# gateway.net
KiCad netlist of a schematic drawn in Altium Designer
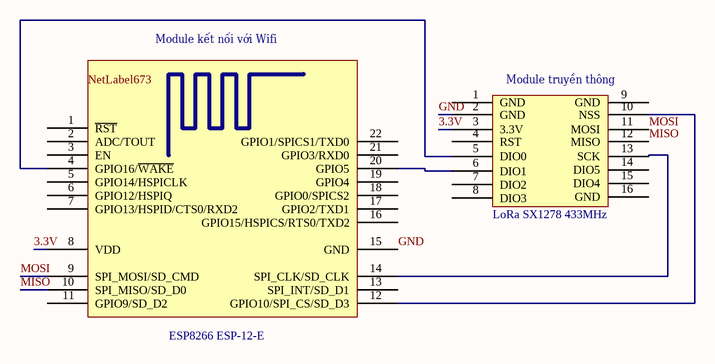
[diagram p0: gateway.SchDoc]

(export (version "E")
  (design (tool "Eeschema 10.0.6"))
  (components
    (comp (ref "Module kết nối với Wifi")
      (value "ESP8266 ESP-12-E")
      (footprint "ESP8266:ESP8266 ESP-12-E")
      (libsource (lib "ESP8266") (part "ESP8266 ESP-12-E"))
    )
    (comp (ref "Module truyền thông")
      (value "LoRa SX1278 433MHz")
      (footprint "PCBLoRa")
      (libsource (lib "LoRa") (part "Component_1"))
    )
  )
  (nets
    (net (code "1") (name "/3.3V") (class "Default")
      (node (ref "Module kết nối với Wifi") (pin "8") (pinfunction "VDD_8") (pintype "passive"))
      (node (ref "Module truyền thông") (pin "3") (pinfunction "3.3V_3") (pintype "passive"))
    )
    (net (code "2") (name "/GND") (class "Default")
      (node (ref "Module kết nối với Wifi") (pin "15") (pinfunction "GND_15") (pintype "passive"))
      (node (ref "Module truyền thông") (pin "2") (pinfunction "GND_2") (pintype "passive"))
    )
    (net (code "3") (name "/MISO") (class "Default")
      (node (ref "Module kết nối với Wifi") (pin "10") (pinfunction "SPI_MISO/SD_D0_10") (pintype "passive"))
      (node (ref "Module truyền thông") (pin "12") (pinfunction "MISO_12") (pintype "passive"))
    )
    (net (code "4") (name "/MOSI") (class "Default")
      (node (ref "Module kết nối với Wifi") (pin "9") (pinfunction "SPI_MOSI/SD_CMD_9") (pintype "passive"))
      (node (ref "Module truyền thông") (pin "11") (pinfunction "MOSI_11") (pintype "passive"))
    )
    (net (code "6") (name "Net-(Module kết nối với Wifi-GPIO5)") (class "Default")
      (node (ref "Module kết nối với Wifi") (pin "20") (pinfunction "GPIO5_20") (pintype "passive"))
      (node (ref "Module truyền thông") (pin "6") (pinfunction "DIO1_6") (pintype "passive"))
    )
    (net (code "7") (name "Net-(Module kết nối với Wifi-GPIO10{slash}SPI_CS{slash}SD_D3)") (class "Default")
      (node (ref "Module kết nối với Wifi") (pin "12") (pinfunction "GPIO10/SPI_CS/SD_D3_12") (pintype "passive"))
      (node (ref "Module truyền thông") (pin "10") (pinfunction "NSS_10") (pintype "passive"))
    )
    (net (code "8") (name "Net-(Module kết nối với Wifi-GPIO16{slash}~{WAKE})") (class "Default")
      (node (ref "Module kết nối với Wifi") (pin "4") (pinfunction "GPIO16/~{WAKE}_4") (pintype "passive"))
      (node (ref "Module truyền thông") (pin "5") (pinfunction "DIO0_5") (pintype "passive"))
    )
    (net (code "9") (name "Net-(Module kết nối với Wifi-SPI_CLK{slash}SD_CLK)") (class "Default")
      (node (ref "Module kết nối với Wifi") (pin "14") (pinfunction "SPI_CLK/SD_CLK_14") (pintype "passive"))
      (node (ref "Module truyền thông") (pin "13") (pinfunction "SCK_13") (pintype "passive"))
    )
    (net (code "10") (name "unconnected-(Module kết nối với Wifi-ADC{slash}TOUT-Pad2)") (class "Default")
      (node (ref "Module kết nối với Wifi") (pin "2") (pinfunction "ADC/TOUT_2") (pintype "passive"))
    )
    (net (code "11") (name "unconnected-(Module kết nối với Wifi-EN-Pad3)") (class "Default")
      (node (ref "Module kết nối với Wifi") (pin "3") (pinfunction "EN_3") (pintype "passive"))
    )
    (net (code "12") (name "unconnected-(Module kết nối với Wifi-GPIO0{slash}SPICS2-Pad18)") (class "Default")
      (node (ref "Module kết nối với Wifi") (pin "18") (pinfunction "GPIO0/SPICS2_18") (pintype "passive"))
    )
    (net (code "13") (name "unconnected-(Module kết nối với Wifi-GPIO1{slash}SPICS1{slash}TXD0-Pad22)") (class "Default")
      (node (ref "Module kết nối với Wifi") (pin "22") (pinfunction "GPIO1/SPICS1/TXD0_22") (pintype "passive"))
    )
    (net (code "14") (name "unconnected-(Module kết nối với Wifi-GPIO2{slash}TXD1-Pad17)") (class "Default")
      (node (ref "Module kết nối với Wifi") (pin "17") (pinfunction "GPIO2/TXD1_17") (pintype "passive"))
    )
    (net (code "15") (name "unconnected-(Module kết nối với Wifi-GPIO3{slash}RXD0-Pad21)") (class "Default")
      (node (ref "Module kết nối với Wifi") (pin "21") (pinfunction "GPIO3/RXD0_21") (pintype "passive"))
    )
    (net (code "16") (name "unconnected-(Module kết nối với Wifi-GPIO4-Pad19)") (class "Default")
      (node (ref "Module kết nối với Wifi") (pin "19") (pinfunction "GPIO4_19") (pintype "passive"))
    )
    (net (code "17") (name "unconnected-(Module kết nối với Wifi-GPIO9{slash}SD_D2-Pad11)") (class "Default")
      (node (ref "Module kết nối với Wifi") (pin "11") (pinfunction "GPIO9/SD_D2_11") (pintype "passive"))
    )
    (net (code "18") (name "unconnected-(Module kết nối với Wifi-GPIO12{slash}HSPIQ-Pad6)") (class "Default")
      (node (ref "Module kết nối với Wifi") (pin "6") (pinfunction "GPIO12/HSPIQ_6") (pintype "passive"))
    )
    (net (code "19") (name "unconnected-(Module kết nối với Wifi-GPIO13{slash}HSPID{slash}CTS0{slash}RXD2-Pad7)") (class "Default")
      (node (ref "Module kết nối với Wifi") (pin "7") (pinfunction "GPIO13/HSPID/CTS0/RXD2_7") (pintype "passive"))
    )
    (net (code "20") (name "unconnected-(Module kết nối với Wifi-GPIO14{slash}HSPICLK-Pad5)") (class "Default")
      (node (ref "Module kết nối với Wifi") (pin "5") (pinfunction "GPIO14/HSPICLK_5") (pintype "passive"))
    )
    (net (code "21") (name "unconnected-(Module kết nối với Wifi-GPIO15{slash}HSPICS{slash}RTS0{slash}TXD2-Pad16)") (class "Default")
      (node (ref "Module kết nối với Wifi") (pin "16") (pinfunction "GPIO15/HSPICS/RTS0/TXD2_16") (pintype "passive"))
    )
    (net (code "22") (name "unconnected-(Module kết nối với Wifi-SPI_INT{slash}SD_D1-Pad13)") (class "Default")
      (node (ref "Module kết nối với Wifi") (pin "13") (pinfunction "SPI_INT/SD_D1_13") (pintype "passive"))
    )
    (net (code "23") (name "unconnected-(Module kết nối với Wifi-~{RST}-Pad1)") (class "Default")
      (node (ref "Module kết nối với Wifi") (pin "1") (pinfunction "~{RST}_1") (pintype "passive"))
    )
    (net (code "24") (name "unconnected-(Module truyền thông-DIO2-Pad7)") (class "Default")
      (node (ref "Module truyền thông") (pin "7") (pinfunction "DIO2_7") (pintype "passive"))
    )
    (net (code "25") (name "unconnected-(Module truyền thông-DIO3-Pad8)") (class "Default")
      (node (ref "Module truyền thông") (pin "8") (pinfunction "DIO3_8") (pintype "passive"))
    )
    (net (code "26") (name "unconnected-(Module truyền thông-DIO4-Pad15)") (class "Default")
      (node (ref "Module truyền thông") (pin "15") (pinfunction "DIO4_15") (pintype "passive"))
    )
    (net (code "27") (name "unconnected-(Module truyền thông-DIO5-Pad14)") (class "Default")
      (node (ref "Module truyền thông") (pin "14") (pinfunction "DIO5_14") (pintype "passive"))
    )
    (net (code "28") (name "unconnected-(Module truyền thông-GND-Pad1)") (class "Default")
      (node (ref "Module truyền thông") (pin "1") (pinfunction "GND_1") (pintype "passive"))
    )
    (net (code "29") (name "unconnected-(Module truyền thông-GND-Pad9)") (class "Default")
      (node (ref "Module truyền thông") (pin "9") (pinfunction "GND_9") (pintype "passive"))
    )
    (net (code "30") (name "unconnected-(Module truyền thông-GND-Pad16)") (class "Default")
      (node (ref "Module truyền thông") (pin "16") (pinfunction "GND_16") (pintype "passive"))
    )
    (net (code "31") (name "unconnected-(Module truyền thông-RST-Pad4)") (class "Default")
      (node (ref "Module truyền thông") (pin "4") (pinfunction "RST_4") (pintype "passive"))
    )
  )
)
